# Motors.net
KiCad netlist of a schematic drawn in Altium Designer
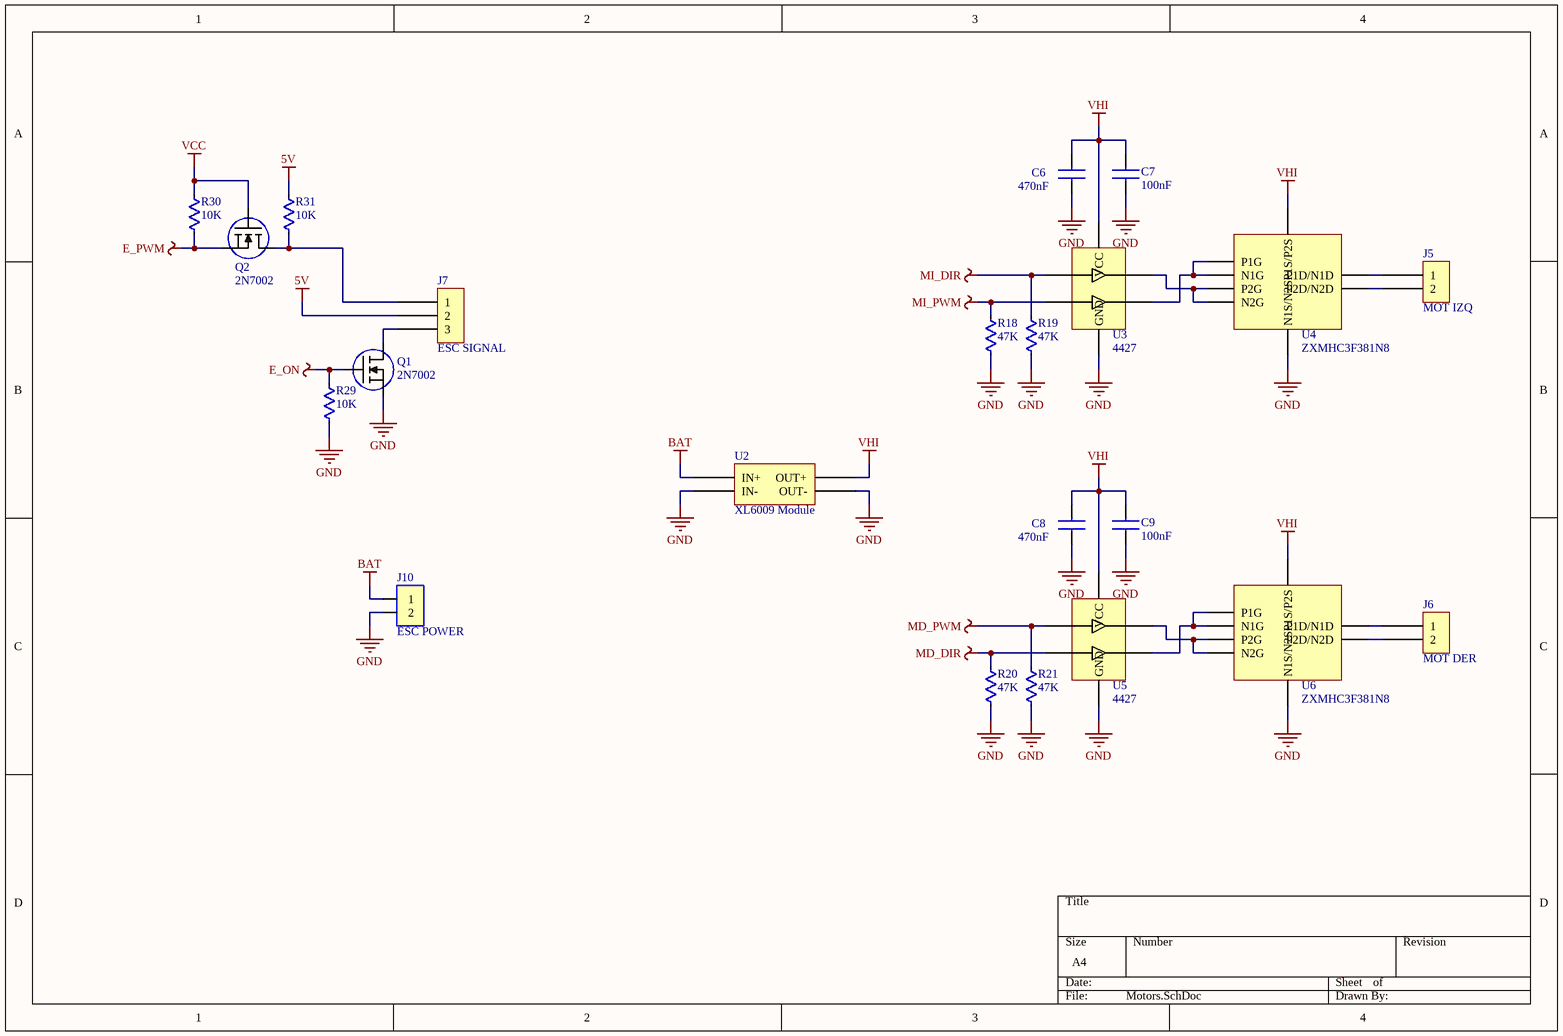
[diagram p0: Motors.SchDoc]

(export (version "E")
  (design (tool "Eeschema 10.0.6"))
  (components
    (comp (ref "C6")
      (value "470nF")
      (footprint "C1206")
      (fields (field (name "Comment") "CAP-CER"))
      (libsource (lib "AltiumLibrary") (part "CAP-CER"))
    )
    (comp (ref "C7")
      (value "100nF")
      (footprint "C1206")
      (fields (field (name "Comment") "CAP-CER"))
      (libsource (lib "AltiumLibrary") (part "CAP-CER"))
    )
    (comp (ref "C8")
      (value "470nF")
      (footprint "C1206")
      (fields (field (name "Comment") "CAP-CER"))
      (libsource (lib "AltiumLibrary") (part "CAP-CER"))
    )
    (comp (ref "C9")
      (value "100nF")
      (footprint "C1206")
      (fields (field (name "Comment") "CAP-CER"))
      (libsource (lib "AltiumLibrary") (part "CAP-CER"))
    )
    (comp (ref "J5")
      (value "MOT IZQ")
      (footprint "HEADER 1x2")
      (libsource (lib "AltiumLibrary") (part "Header 1x2"))
    )
    (comp (ref "J6")
      (value "MOT DER")
      (footprint "HEADER 1x2")
      (libsource (lib "AltiumLibrary") (part "Header 1x2"))
    )
    (comp (ref "J7")
      (value "ESC SIGNAL")
      (footprint "Header 1x3")
      (libsource (lib "AltiumLibrary") (part "Header 1x3"))
    )
    (comp (ref "J10")
      (value "ESC POWER")
      (footprint "BLOCK_TERMINAL-2")
      (libsource (lib "AltiumLibrary") (part "2-BLOCK_TERMINAL"))
    )
    (comp (ref "Q1")
      (value "2N7002")
      (footprint "SOT-23")
      (libsource (lib "AltiumLibrary") (part "N-MOSFET"))
    )
    (comp (ref "Q2")
      (value "2N7002")
      (footprint "SOT-23")
      (libsource (lib "AltiumLibrary") (part "N-MOSFET"))
    )
    (comp (ref "R18")
      (value "47K")
      (footprint "R1206")
      (fields (field (name "Comment") "RES"))
      (libsource (lib "AltiumLibrary") (part "RES"))
    )
    (comp (ref "R19")
      (value "47K")
      (footprint "R1206")
      (fields (field (name "Comment") "RES"))
      (libsource (lib "AltiumLibrary") (part "RES"))
    )
    (comp (ref "R20")
      (value "47K")
      (footprint "R1206")
      (fields (field (name "Comment") "RES"))
      (libsource (lib "AltiumLibrary") (part "RES"))
    )
    (comp (ref "R21")
      (value "47K")
      (footprint "R1206")
      (fields (field (name "Comment") "RES"))
      (libsource (lib "AltiumLibrary") (part "RES"))
    )
    (comp (ref "R29")
      (value "10K")
      (footprint "R1206")
      (fields (field (name "Comment") "RES"))
      (libsource (lib "AltiumLibrary") (part "RES"))
    )
    (comp (ref "R30")
      (value "10K")
      (footprint "R1206")
      (fields (field (name "Comment") "RES"))
      (libsource (lib "AltiumLibrary") (part "RES"))
    )
    (comp (ref "R31")
      (value "10K")
      (footprint "R1206")
      (fields (field (name "Comment") "RES"))
      (libsource (lib "AltiumLibrary") (part "RES"))
    )
    (comp (ref "U2")
      (value "XL6009 Module")
      (footprint "XL6009 mdl")
      (libsource (lib "AltiumLibrary") (part "XL6009 Module"))
    )
    (comp (ref "U3") (value "4427") (footprint "SOIC-8") (libsource (lib "AltiumLibrary") (part "4427")))
    (comp (ref "U4")
      (value "ZXMHC3F381N8")
      (footprint "SOIC-8")
      (libsource (lib "AltiumLibrary") (part "ZXMHC3F381N8"))
    )
    (comp (ref "U5") (value "4427") (footprint "SOIC-8") (libsource (lib "AltiumLibrary") (part "4427")))
    (comp (ref "U6")
      (value "ZXMHC3F381N8")
      (footprint "SOIC-8")
      (libsource (lib "AltiumLibrary") (part "ZXMHC3F381N8"))
    )
  )
  (nets
    (net (code "1") (name "5V") (class "Default")
      (node (ref "J7") (pin "2") (pinfunction "2_2") (pintype "passive"))
      (node (ref "R31") (pin "2") (pintype "passive"))
    )
    (net (code "2") (name "BAT") (class "Default")
      (node (ref "J10") (pin "1") (pinfunction "1_1") (pintype "passive"))
      (node (ref "U2") (pin "0") (pinfunction "IN+_0") (pintype "passive"))
    )
    (net (code "3") (name "E_ON") (class "Default")
      (node (ref "Q1") (pin "G") (pintype "passive"))
      (node (ref "R29") (pin "2") (pintype "passive"))
    )
    (net (code "4") (name "E_PWM") (class "Default")
      (node (ref "Q2") (pin "S") (pintype "passive"))
      (node (ref "R30") (pin "1") (pintype "passive"))
    )
    (net (code "5") (name "GND") (class "Default")
      (node (ref "C6") (pin "1") (pintype "passive"))
      (node (ref "C7") (pin "1") (pintype "passive"))
      (node (ref "C8") (pin "1") (pintype "passive"))
      (node (ref "C9") (pin "1") (pintype "passive"))
      (node (ref "J10") (pin "2") (pinfunction "2_2") (pintype "passive"))
      (node (ref "Q1") (pin "S") (pintype "passive"))
      (node (ref "R18") (pin "1") (pintype "passive"))
      (node (ref "R19") (pin "1") (pintype "passive"))
      (node (ref "R20") (pin "1") (pintype "passive"))
      (node (ref "R21") (pin "1") (pintype "passive"))
      (node (ref "R29") (pin "1") (pintype "passive"))
      (node (ref "U2") (pin "1") (pinfunction "IN-_1") (pintype "passive"))
      (node (ref "U2") (pin "2") (pinfunction "OUT-_2") (pintype "passive"))
      (node (ref "U3") (pin "3") (pinfunction "GND_3") (pintype "passive"))
      (node (ref "U4") (pin "3") (pinfunction "N1S/N2S_3") (pintype "passive"))
      (node (ref "U5") (pin "3") (pinfunction "GND_3") (pintype "passive"))
      (node (ref "U6") (pin "3") (pinfunction "N1S/N2S_3") (pintype "passive"))
    )
    (net (code "6") (name "MD_DIR") (class "Default")
      (node (ref "R20") (pin "2") (pintype "passive"))
      (node (ref "U5") (pin "4") (pinfunction "INB_4") (pintype "passive"))
    )
    (net (code "7") (name "MD_PWM") (class "Default")
      (node (ref "R21") (pin "2") (pintype "passive"))
      (node (ref "U5") (pin "2") (pinfunction "INA_2") (pintype "passive"))
    )
    (net (code "8") (name "MI_DIR") (class "Default")
      (node (ref "R19") (pin "2") (pintype "passive"))
      (node (ref "U3") (pin "2") (pinfunction "INA_2") (pintype "passive"))
    )
    (net (code "9") (name "MI_PWM") (class "Default")
      (node (ref "R18") (pin "2") (pintype "passive"))
      (node (ref "U3") (pin "4") (pinfunction "INB_4") (pintype "passive"))
    )
    (net (code "10") (name "Net-(J7-Pad1)") (class "Default")
      (node (ref "J7") (pin "1") (pinfunction "1_1") (pintype "passive"))
      (node (ref "Q2") (pin "D") (pintype "passive"))
      (node (ref "R31") (pin "1") (pintype "passive"))
    )
    (net (code "11") (name "Net-(J7-Pad3)") (class "Default")
      (node (ref "J7") (pin "3") (pinfunction "3_3") (pintype "passive"))
      (node (ref "Q1") (pin "D") (pintype "passive"))
    )
    (net (code "12") (name "Net-(U3-OUTA)") (class "Default")
      (node (ref "U3") (pin "7") (pinfunction "OUTA_7") (pintype "passive"))
      (node (ref "U4") (pin "4") (pinfunction "N2G_4") (pintype "passive"))
      (node (ref "U4") (pin "5") (pinfunction "P2G_5") (pintype "passive"))
    )
    (net (code "13") (name "Net-(U3-OUTB)") (class "Default")
      (node (ref "U3") (pin "5") (pinfunction "OUTB_5") (pintype "passive"))
      (node (ref "U4") (pin "1") (pinfunction "N1G_1") (pintype "passive"))
      (node (ref "U4") (pin "8") (pinfunction "P1G_8") (pintype "passive"))
    )
    (net (code "14") (name "Net-(U4-P1D{slash}N1D)") (class "Default")
      (node (ref "J5") (pin "1") (pinfunction "1_1") (pintype "passive"))
      (node (ref "U4") (pin "2") (pinfunction "P1D/N1D_2") (pintype "passive"))
    )
    (net (code "15") (name "Net-(U4-P2D{slash}N2D)") (class "Default")
      (node (ref "J5") (pin "2") (pinfunction "2_2") (pintype "passive"))
      (node (ref "U4") (pin "6") (pinfunction "P2D/N2D_6") (pintype "passive"))
    )
    (net (code "16") (name "Net-(U5-OUTA)") (class "Default")
      (node (ref "U5") (pin "7") (pinfunction "OUTA_7") (pintype "passive"))
      (node (ref "U6") (pin "4") (pinfunction "N2G_4") (pintype "passive"))
      (node (ref "U6") (pin "5") (pinfunction "P2G_5") (pintype "passive"))
    )
    (net (code "17") (name "Net-(U5-OUTB)") (class "Default")
      (node (ref "U5") (pin "5") (pinfunction "OUTB_5") (pintype "passive"))
      (node (ref "U6") (pin "1") (pinfunction "N1G_1") (pintype "passive"))
      (node (ref "U6") (pin "8") (pinfunction "P1G_8") (pintype "passive"))
    )
    (net (code "18") (name "Net-(U6-P1D{slash}N1D)") (class "Default")
      (node (ref "J6") (pin "1") (pinfunction "1_1") (pintype "passive"))
      (node (ref "U6") (pin "2") (pinfunction "P1D/N1D_2") (pintype "passive"))
    )
    (net (code "19") (name "Net-(U6-P2D{slash}N2D)") (class "Default")
      (node (ref "J6") (pin "2") (pinfunction "2_2") (pintype "passive"))
      (node (ref "U6") (pin "6") (pinfunction "P2D/N2D_6") (pintype "passive"))
    )
    (net (code "20") (name "VCC") (class "Default")
      (node (ref "Q2") (pin "G") (pintype "passive"))
      (node (ref "R30") (pin "2") (pintype "passive"))
    )
    (net (code "21") (name "VHI") (class "Default")
      (node (ref "C6") (pin "2") (pintype "passive"))
      (node (ref "C7") (pin "2") (pintype "passive"))
      (node (ref "C8") (pin "2") (pintype "passive"))
      (node (ref "C9") (pin "2") (pintype "passive"))
      (node (ref "U2") (pin "3") (pinfunction "OUT+_3") (pintype "passive"))
      (node (ref "U3") (pin "6") (pinfunction "VCC_6") (pintype "passive"))
      (node (ref "U4") (pin "7") (pinfunction "P1S/P2S_7") (pintype "passive"))
      (node (ref "U5") (pin "6") (pinfunction "VCC_6") (pintype "passive"))
      (node (ref "U6") (pin "7") (pinfunction "P1S/P2S_7") (pintype "passive"))
    )
  )
)
